# ProProject_audio_project_2024-04-28.net
KiCad netlist of a schematic drawn in EasyEDA Pro
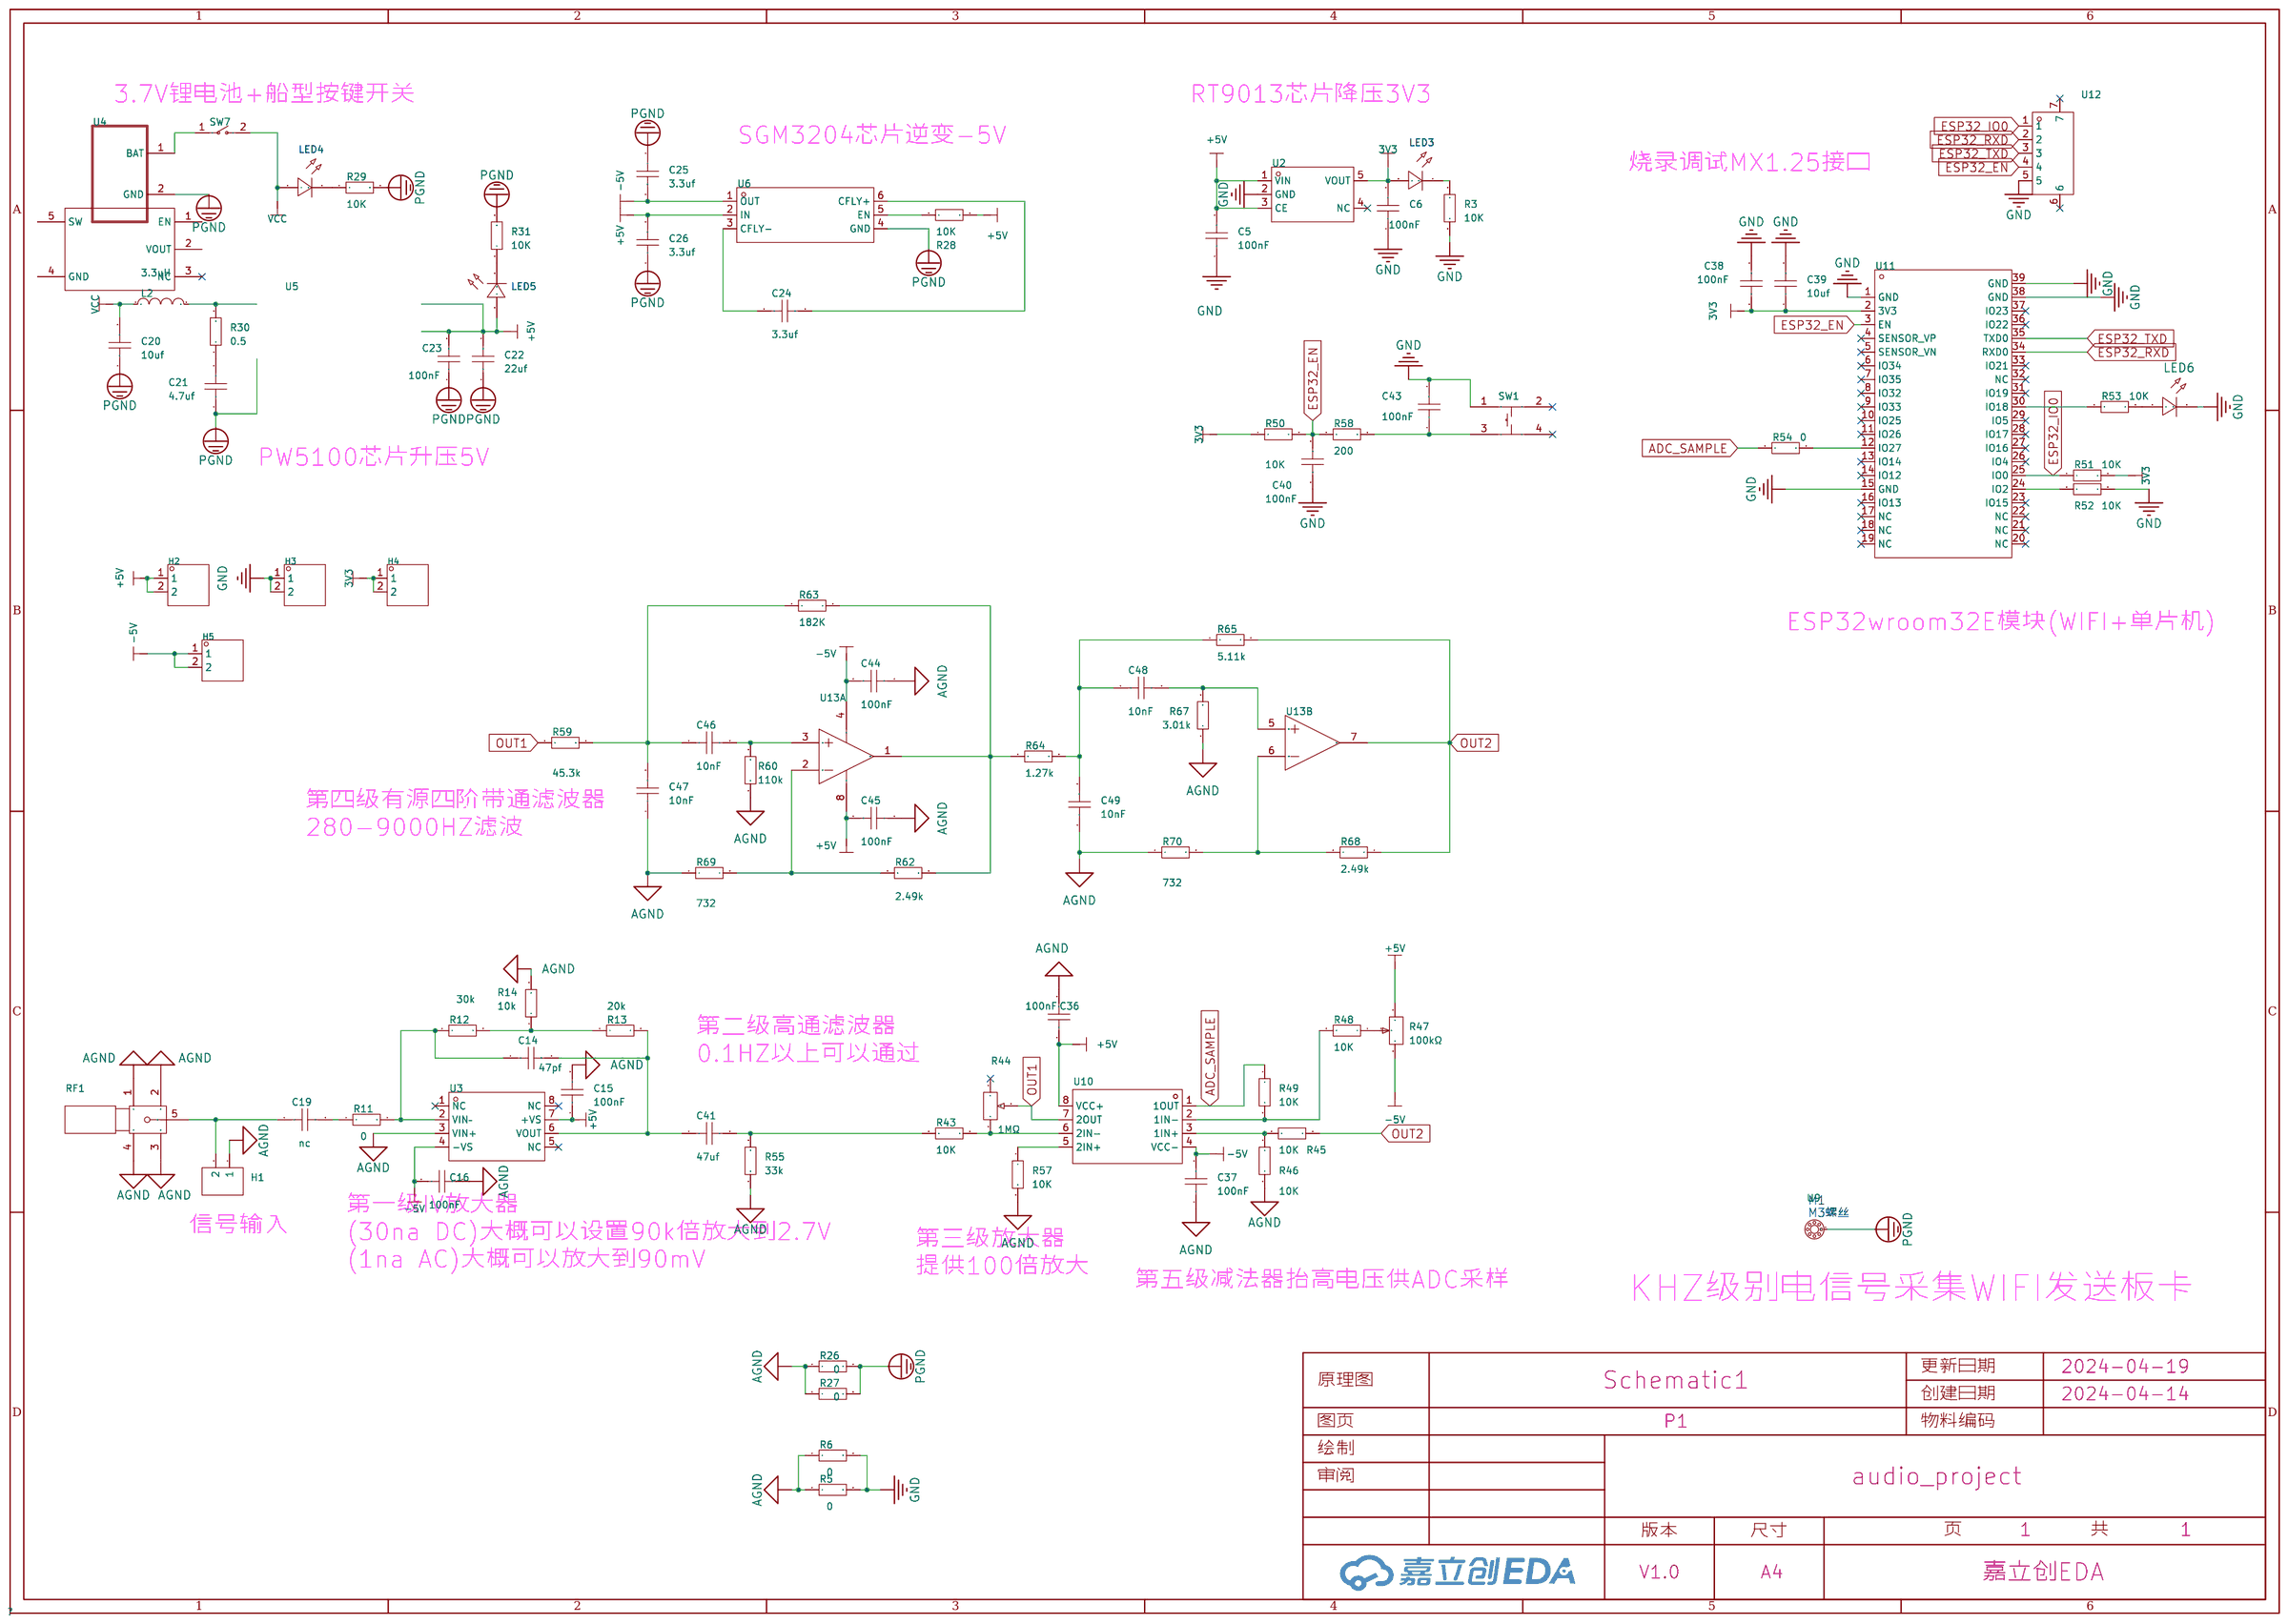
[diagram p0: schematic sheet]

(export (version "E")
  (design (tool "Eeschema 10.0.6"))
  (components
    (comp (ref "C5")
      (value "100nF")
      (footprint "easyedapro:C0805")
      (libsource (lib "easyedapro") (part "CapAcitance"))
    )
    (comp (ref "C6")
      (value "100nF")
      (footprint "easyedapro:C0805")
      (libsource (lib "easyedapro") (part "CapAcitance"))
    )
    (comp (ref "C14")
      (value "47pf")
      (footprint "easyedapro:C0805")
      (libsource (lib "easyedapro") (part "CapAcitance"))
    )
    (comp (ref "C15")
      (value "100nF")
      (footprint "easyedapro:C0805")
      (libsource (lib "easyedapro") (part "CapAcitance"))
    )
    (comp (ref "C16")
      (value "100nF")
      (footprint "easyedapro:C0805")
      (libsource (lib "easyedapro") (part "CapAcitance"))
    )
    (comp (ref "C19")
      (value "nc")
      (footprint "easyedapro:C0805")
      (libsource (lib "easyedapro") (part "CapAcitance"))
    )
    (comp (ref "C20")
      (value "10uf")
      (footprint "easyedapro:C0805")
      (libsource (lib "easyedapro") (part "CapAcitance"))
    )
    (comp (ref "C21")
      (value "4.7uf")
      (footprint "easyedapro:C0805")
      (libsource (lib "easyedapro") (part "CapAcitance"))
    )
    (comp (ref "C22")
      (value "22uf")
      (footprint "easyedapro:C0805")
      (libsource (lib "easyedapro") (part "CapAcitance"))
    )
    (comp (ref "C23")
      (value "100nF")
      (footprint "easyedapro:C0805")
      (libsource (lib "easyedapro") (part "CapAcitance"))
    )
    (comp (ref "C24")
      (value "3.3uf")
      (footprint "easyedapro:C0805")
      (libsource (lib "easyedapro") (part "CapAcitance"))
    )
    (comp (ref "C25")
      (value "3.3uf")
      (footprint "easyedapro:C0805")
      (libsource (lib "easyedapro") (part "CapAcitance"))
    )
    (comp (ref "C26")
      (value "3.3uf")
      (footprint "easyedapro:C0805")
      (libsource (lib "easyedapro") (part "CapAcitance"))
    )
    (comp (ref "C36")
      (value "100nF")
      (footprint "easyedapro:C0805")
      (libsource (lib "easyedapro") (part "CapAcitance"))
    )
    (comp (ref "C37")
      (value "100nF")
      (footprint "easyedapro:C0805")
      (libsource (lib "easyedapro") (part "CapAcitance"))
    )
    (comp (ref "C38")
      (value "100nF")
      (footprint "easyedapro:C0805")
      (libsource (lib "easyedapro") (part "CapAcitance"))
    )
    (comp (ref "C39")
      (value "10uf")
      (footprint "easyedapro:C0805")
      (libsource (lib "easyedapro") (part "CapAcitance"))
    )
    (comp (ref "C40")
      (value "100nF")
      (footprint "easyedapro:C0805")
      (libsource (lib "easyedapro") (part "CapAcitance"))
    )
    (comp (ref "C41")
      (value "47uf")
      (footprint "easyedapro:C0805")
      (libsource (lib "easyedapro") (part "CapAcitance"))
    )
    (comp (ref "C43")
      (value "100nF")
      (footprint "easyedapro:C0805")
      (libsource (lib "easyedapro") (part "CapAcitance"))
    )
    (comp (ref "C44")
      (value "100nF")
      (footprint "easyedapro:C0805")
      (libsource (lib "easyedapro") (part "CapAcitance"))
    )
    (comp (ref "C45")
      (value "100nF")
      (footprint "easyedapro:C0805")
      (libsource (lib "easyedapro") (part "CapAcitance"))
    )
    (comp (ref "C46")
      (value "10nF")
      (footprint "easyedapro:C0805")
      (libsource (lib "easyedapro") (part "CapAcitance"))
    )
    (comp (ref "C47")
      (value "10nF")
      (footprint "easyedapro:C0805")
      (libsource (lib "easyedapro") (part "CapAcitance"))
    )
    (comp (ref "C48")
      (value "10nF")
      (footprint "easyedapro:C0805")
      (libsource (lib "easyedapro") (part "CapAcitance"))
    )
    (comp (ref "C49")
      (value "10nF")
      (footprint "easyedapro:C0805")
      (libsource (lib "easyedapro") (part "CapAcitance"))
    )
    (comp (ref "H1")
      (value "~")
      (footprint "easyedapro:HDR-TH_2P-P2.54-V-F")
      (libsource (lib "easyedapro") (part "Header-Female-2.54_1x2"))
    )
    (comp (ref "H2")
      (value "~")
      (footprint "easyedapro:HDR-TH_2P-P2.54-V-M-1")
      (libsource (lib "easyedapro") (part "210S-1*2P L=11.6MMGold-plated black"))
    )
    (comp (ref "H3")
      (value "~")
      (footprint "easyedapro:HDR-TH_2P-P2.54-V-M-1")
      (libsource (lib "easyedapro") (part "210S-1*2P L=11.6MMGold-plated black"))
    )
    (comp (ref "H4")
      (value "~")
      (footprint "easyedapro:HDR-TH_2P-P2.54-V-M-1")
      (libsource (lib "easyedapro") (part "210S-1*2P L=11.6MMGold-plated black"))
    )
    (comp (ref "H5")
      (value "~")
      (footprint "easyedapro:HDR-TH_2P-P2.54-V-M-1")
      (libsource (lib "easyedapro") (part "210S-1*2P L=11.6MMGold-plated black"))
    )
    (comp (ref "L2")
      (value "3.3uH")
      (footprint "easyedapro:IND-SMD_L4.0-W4.0_FNR40XXS")
      (description "电感值:3.3uH;精度:±20%;额定电流:2.6A;饱和电流(Isat):3.6A;")
      (fields (field (name "Manufacturer Part") "FNR4030S3R3MT") (field (name "Manufacturer") "cjiang(长江微电)"))
      (libsource (lib "easyedapro") (part "FNR4030S3R3MT"))
    )
    (comp (ref "LED3")
      (value "~")
      (footprint "easyedapro:LED_0805")
      (libsource (lib "easyedapro") (part "LED_G"))
    )
    (comp (ref "LED4")
      (value "~")
      (footprint "easyedapro:LED_0805")
      (libsource (lib "easyedapro") (part "LED_G"))
    )
    (comp (ref "LED5")
      (value "~")
      (footprint "easyedapro:LED_0805")
      (libsource (lib "easyedapro") (part "LED_G"))
    )
    (comp (ref "LED6")
      (value "~")
      (footprint "easyedapro:LED_0805")
      (libsource (lib "easyedapro") (part "LED_R"))
    )
    (comp (ref "R3") (value "10K") (footprint "easyedapro:R0603") (libsource (lib "easyedapro") (part "电阻")))
    (comp (ref "R5") (value "0") (footprint "easyedapro:R0603") (libsource (lib "easyedapro") (part "电阻")))
    (comp (ref "R6") (value "0") (footprint "easyedapro:R0603") (libsource (lib "easyedapro") (part "电阻")))
    (comp (ref "R11") (value "0") (footprint "easyedapro:R0603") (libsource (lib "easyedapro") (part "电阻")))
    (comp (ref "R12") (value "30k") (footprint "easyedapro:R0603") (libsource (lib "easyedapro") (part "电阻")))
    (comp (ref "R13") (value "20k") (footprint "easyedapro:R0603") (libsource (lib "easyedapro") (part "电阻")))
    (comp (ref "R14") (value "10k") (footprint "easyedapro:R0603") (libsource (lib "easyedapro") (part "电阻")))
    (comp (ref "R26") (value "0") (footprint "easyedapro:R0603") (libsource (lib "easyedapro") (part "电阻")))
    (comp (ref "R27") (value "0") (footprint "easyedapro:R0603") (libsource (lib "easyedapro") (part "电阻")))
    (comp (ref "R28") (value "10K") (footprint "easyedapro:R0603") (libsource (lib "easyedapro") (part "电阻")))
    (comp (ref "R29") (value "10K") (footprint "easyedapro:R0603") (libsource (lib "easyedapro") (part "电阻")))
    (comp (ref "R30") (value "0.5") (footprint "easyedapro:R0603") (libsource (lib "easyedapro") (part "电阻")))
    (comp (ref "R31") (value "10K") (footprint "easyedapro:R0603") (libsource (lib "easyedapro") (part "电阻")))
    (comp (ref "R43") (value "10K") (footprint "easyedapro:R0603") (libsource (lib "easyedapro") (part "电阻")))
    (comp (ref "R44")
      (value "1MΩ")
      (footprint "easyedapro:RES-ADJ-TH_3P-L7.1-W6.9-P2.50-L_3362P")
      (description "阻值:1MΩ;精度:±10%;")
      (fields (field (name "Manufacturer Part") "3362P-1-105") (field (name "Manufacturer") "BOCHEN(博晨)"))
      (libsource (lib "easyedapro") (part "3362P-1-105_C118945"))
    )
    (comp (ref "R45") (value "10K") (footprint "easyedapro:R0603") (libsource (lib "easyedapro") (part "电阻")))
    (comp (ref "R46") (value "10K") (footprint "easyedapro:R0603") (libsource (lib "easyedapro") (part "电阻")))
    (comp (ref "R47")
      (value "100kΩ")
      (footprint "easyedapro:RES-ADJ-TH_3296W")
      (description "阻值:100kΩ;精度:±10%;")
      (fields (field (name "Manufacturer Part") "3296W-1-104LF") (field (name "Manufacturer") "BOURNS"))
      (libsource (lib "easyedapro") (part "3296W-1-104LF"))
    )
    (comp (ref "R48") (value "10K") (footprint "easyedapro:R0603") (libsource (lib "easyedapro") (part "电阻")))
    (comp (ref "R49") (value "10K") (footprint "easyedapro:R0603") (libsource (lib "easyedapro") (part "电阻")))
    (comp (ref "R50") (value "10K") (footprint "easyedapro:R0603") (libsource (lib "easyedapro") (part "电阻")))
    (comp (ref "R51") (value "10K") (footprint "easyedapro:R0603") (libsource (lib "easyedapro") (part "电阻")))
    (comp (ref "R52") (value "10K") (footprint "easyedapro:R0603") (libsource (lib "easyedapro") (part "电阻")))
    (comp (ref "R53") (value "10K") (footprint "easyedapro:R0603") (libsource (lib "easyedapro") (part "电阻")))
    (comp (ref "R54") (value "0") (footprint "easyedapro:R0603") (libsource (lib "easyedapro") (part "电阻")))
    (comp (ref "R55") (value "33k") (footprint "easyedapro:R0603") (libsource (lib "easyedapro") (part "电阻")))
    (comp (ref "R57") (value "10K") (footprint "easyedapro:R0603") (libsource (lib "easyedapro") (part "电阻")))
    (comp (ref "R58") (value "200") (footprint "easyedapro:R0603") (libsource (lib "easyedapro") (part "电阻")))
    (comp (ref "R59")
      (value "45.3k")
      (footprint "easyedapro:R0603")
      (libsource (lib "easyedapro") (part "电阻"))
    )
    (comp (ref "R60")
      (value "110k")
      (footprint "easyedapro:R0603")
      (libsource (lib "easyedapro") (part "电阻"))
    )
    (comp (ref "R62")
      (value "2.49k")
      (footprint "easyedapro:R0603")
      (libsource (lib "easyedapro") (part "电阻"))
    )
    (comp (ref "R63")
      (value "182K")
      (footprint "easyedapro:R0603")
      (libsource (lib "easyedapro") (part "电阻"))
    )
    (comp (ref "R64")
      (value "1.27k")
      (footprint "easyedapro:R0603")
      (libsource (lib "easyedapro") (part "电阻"))
    )
    (comp (ref "R65")
      (value "5.11k")
      (footprint "easyedapro:R0603")
      (libsource (lib "easyedapro") (part "电阻"))
    )
    (comp (ref "R67")
      (value "3.01k")
      (footprint "easyedapro:R0603")
      (libsource (lib "easyedapro") (part "电阻"))
    )
    (comp (ref "R68")
      (value "2.49k")
      (footprint "easyedapro:R0603")
      (libsource (lib "easyedapro") (part "电阻"))
    )
    (comp (ref "R69") (value "732") (footprint "easyedapro:R0603") (libsource (lib "easyedapro") (part "电阻")))
    (comp (ref "R70") (value "732") (footprint "easyedapro:R0603") (libsource (lib "easyedapro") (part "电阻")))
    (comp (ref "RF1")
      (value "BWSMA-KWE-Z001")
      (footprint "easyedapro:SMA-TH_BWSMA-KWE-Z001")
      (fields (field (name "Manufacturer") "BAT WIRELESS(蝙蝠无线)"))
      (libsource (lib "easyedapro") (part "BWSMA-KWE-Z001"))
    )
    (comp (ref "SW1")
      (value "K2-1808SN-A3SW-01")
      (footprint "easyedapro:SW-SMD_4P-L4.2-W3.3-P2.15-LS5.1")
      (fields (field (name "Manufacturer") "韩国韩荣"))
      (libsource (lib "easyedapro") (part "K2-1808SN-A3SW-01"))
    )
    (comp (ref "SW7")
      (value "KCD11-2P-R")
      (footprint "easyedapro:SW-TH_2P-L15.0-W10.5-P5.00_KCD11-2P-R")
      (description "带灯:无;引脚样式:焊片;额定电流:3A;额定电压(AC):250V;额定电压(DC):-;电路结构:单刀单掷;机械寿命:1万次;")
      (fields (field (name "Manufacturer") "SHOU HAN(首韩)"))
      (libsource (lib "easyedapro") (part "KCD11-2P-R"))
    )
    (comp (ref "U2")
      (value "RT9013-33GB-MS")
      (footprint "easyedapro:SOT-23-5_L2.9-W1.6-P0.95-LS2.8-BR")
      (description "输出类型:固定;最大输入电压:5.5V;输出电压:3.3V;输出电流:500mA;电源纹波抑制比(PSRR):75dB@(1kHz);输出极性:正极;")
      (fields (field (name "Manufacturer") "MSKSEMI(美森科)"))
      (libsource (lib "easyedapro") (part "RT9013-33GB-MS"))
    )
    (comp (ref "U3")
      (value "OPA657U")
      (footprint "easyedapro:SOIC-8_L4.9-W3.9-P1.27-LS6.0-TL")
      (description "1.6GHz、低噪声、FET 输入运算放大器 8-SOIC -40 to 85")
      (fields (field (name "Manufacturer") "TI(德州仪器)"))
      (libsource (lib "easyedapro") (part "OPA657U"))
    )
    (comp (ref "U4") (value "~") (footprint "easyedapro:两个焊盘") (libsource (lib "easyedapro") (part "两个焊盘")))
    (comp (ref "U5")
      (value "3c0bada92d29401ea73ee46ec49cffd6")
      (footprint "easyedapro:SOT-23-5_L2.9-W1.6-P0.95-LS2.8-TL")
      (description "锂电池DC-DC高效同步升压变换器")
      (libsource (lib "easyedapro") (part "PW5100"))
    )
    (comp (ref "U6")
      (value "SGM3204YN6G/TR")
      (footprint "easyedapro:SOT-23-6_L2.9-W1.6-P0.95-LS2.8-BR")
      (description "功能类型:电荷泵;输入电压:1.4V~5.5V;输出电压:-5.5V~-1.4V;输出电流(最大值):200mA;")
      (fields (field (name "Manufacturer") "SGMICRO(圣邦微)"))
      (libsource (lib "easyedapro") (part "SGM3204YN6G/TR"))
    )
    (comp (ref "U9") (value "~") (libsource (lib "easyedapro") (part "M3焊盘")))
    (comp (ref "U10")
      (value "LF353DR")
      (footprint "easyedapro:SOIC-8_L5.0-W4.0-P1.27-LS6.0-BL")
      (description "运放类型:J-FET;放大器组数:2;增益带宽积（GBP）:3MHz;压摆率（SR）:13 V/us;电源电压:±3.5V ~ 18V;各通道供电电流:3.6mA;")
      (fields (field (name "Manufacturer") "TI(德州仪器)"))
      (libsource (lib "easyedapro") (part "LF353DRG4"))
    )
    (comp (ref "U11")
      (value "ESP32-WROOM-32E")
      (footprint "easyedapro:WIFI-SMD_ESP32-WROOM-32E-A")
      (fields (field (name "Manufacturer") "ESPRESSIF(乐鑫)"))
      (libsource (lib "easyedapro") (part "ESP32-WROOM-32E-N4"))
    )
    (comp (ref "U12")
      (value "ZX-MX1.25-5PLT")
      (footprint "easyedapro:CONN-SMD_5P-P1.25_MEGASTAR_ZX-MX1.25-5PLT")
      (fields (field (name "Manufacturer") "Megastar(兆星)"))
      (libsource (lib "easyedapro") (part "ZX-MX1.25-5PLT"))
    )
    (comp (ref "U13")
      (value "OPA2182IDR")
      (footprint "easyedapro:SOIC-8_L4.9-W3.9-P1.27-LS6.0-BL")
      (description "放大器数:双路;增益带宽积(GBP):5MHz;输入偏置电流(Ib):50pA;输入失调电压(Vos):450nV;压摆率(SR):10V/us;带宽(-3db):-;轨到轨:-;")
      (fields (field (name "Manufacturer") "TI(德州仪器)"))
      (libsource (lib "easyedapro") (part "OPA2182IDR"))
    )
  )
  (nets
    (net (code "1") (name "+5V") (class "Default")
      (node (ref "C15") (pin "1") (pinfunction "1_1") (pintype "input"))
      (node (ref "C22") (pin "2") (pinfunction "2_2") (pintype "input"))
      (node (ref "C23") (pin "2") (pinfunction "2_2") (pintype "input"))
      (node (ref "C26") (pin "2") (pinfunction "2_2") (pintype "input"))
      (node (ref "C36") (pin "1") (pinfunction "1_1") (pintype "input"))
      (node (ref "C45") (pin "2") (pinfunction "2_2") (pintype "input"))
      (node (ref "C5") (pin "2") (pinfunction "2_2") (pintype "input"))
      (node (ref "H2") (pin "1") (pinfunction "1_1") (pintype "input"))
      (node (ref "H2") (pin "2") (pinfunction "2_2") (pintype "input"))
      (node (ref "LED5") (pin "2") (pinfunction "A_2") (pintype "input"))
      (node (ref "R28") (pin "2") (pinfunction "2_2") (pintype "input"))
      (node (ref "R47") (pin "1") (pinfunction "1_1") (pintype "input"))
      (node (ref "U10") (pin "8") (pinfunction "VCC+_8") (pintype "input"))
      (node (ref "U13") (pin "8") (pinfunction "V+_8") (pintype "unspecified"))
      (node (ref "U2") (pin "1") (pinfunction "VIN_1") (pintype "unspecified"))
      (node (ref "U2") (pin "3") (pinfunction "CE_3") (pintype "unspecified"))
      (node (ref "U3") (pin "7") (pinfunction "+VS_7") (pintype "input"))
      (node (ref "U6") (pin "2") (pinfunction "IN_2") (pintype "unspecified"))
    )
    (net (code "2") (name "-5V") (class "Default")
      (node (ref "C16") (pin "2") (pinfunction "2_2") (pintype "input"))
      (node (ref "C25") (pin "2") (pinfunction "2_2") (pintype "input"))
      (node (ref "C37") (pin "2") (pinfunction "2_2") (pintype "input"))
      (node (ref "C44") (pin "2") (pinfunction "2_2") (pintype "input"))
      (node (ref "H5") (pin "1") (pinfunction "1_1") (pintype "input"))
      (node (ref "H5") (pin "2") (pinfunction "2_2") (pintype "input"))
      (node (ref "R47") (pin "3") (pinfunction "3_3") (pintype "input"))
      (node (ref "U10") (pin "4") (pinfunction "VCC-_4") (pintype "input"))
      (node (ref "U13") (pin "4") (pinfunction "V-_4") (pintype "unspecified"))
      (node (ref "U3") (pin "4") (pinfunction "-VS_4") (pintype "input"))
      (node (ref "U6") (pin "1") (pinfunction "OUT_1") (pintype "unspecified"))
    )
    (net (code "3") (name "3V3") (class "Default")
      (node (ref "C38") (pin "2") (pinfunction "2_2") (pintype "input"))
      (node (ref "C39") (pin "1") (pinfunction "1_1") (pintype "input"))
      (node (ref "C6") (pin "2") (pinfunction "2_2") (pintype "input"))
      (node (ref "H4") (pin "1") (pinfunction "1_1") (pintype "input"))
      (node (ref "H4") (pin "2") (pinfunction "2_2") (pintype "input"))
      (node (ref "LED3") (pin "2") (pinfunction "A_2") (pintype "input"))
      (node (ref "R50") (pin "1") (pinfunction "1_1") (pintype "input"))
      (node (ref "R51") (pin "2") (pinfunction "2_2") (pintype "input"))
      (node (ref "U11") (pin "2") (pinfunction "3V3_2") (pintype "unspecified"))
      (node (ref "U2") (pin "5") (pinfunction "VOUT_5") (pintype "unspecified"))
    )
    (net (code "4") (name "ADC_SAMPLE") (class "Default")
      (node (ref "R49") (pin "1") (pinfunction "1_1") (pintype "input"))
      (node (ref "R54") (pin "1") (pinfunction "1_1") (pintype "input"))
      (node (ref "U10") (pin "1") (pinfunction "1OUT_1") (pintype "input"))
    )
    (net (code "5") (name "AGND") (class "Default")
      (node (ref "C15") (pin "2") (pinfunction "2_2") (pintype "input"))
      (node (ref "C16") (pin "1") (pinfunction "1_1") (pintype "input"))
      (node (ref "C36") (pin "2") (pinfunction "2_2") (pintype "input"))
      (node (ref "C37") (pin "1") (pinfunction "1_1") (pintype "input"))
      (node (ref "C44") (pin "1") (pinfunction "1_1") (pintype "input"))
      (node (ref "C45") (pin "1") (pinfunction "1_1") (pintype "input"))
      (node (ref "C47") (pin "1") (pinfunction "1_1") (pintype "input"))
      (node (ref "C49") (pin "1") (pinfunction "1_1") (pintype "input"))
      (node (ref "H1") (pin "1") (pinfunction "1_1") (pintype "input"))
      (node (ref "R14") (pin "2") (pinfunction "2_2") (pintype "input"))
      (node (ref "R26") (pin "1") (pinfunction "1_1") (pintype "input"))
      (node (ref "R27") (pin "1") (pinfunction "1_1") (pintype "input"))
      (node (ref "R46") (pin "1") (pinfunction "1_1") (pintype "input"))
      (node (ref "R5") (pin "1") (pinfunction "1_1") (pintype "input"))
      (node (ref "R55") (pin "1") (pinfunction "1_1") (pintype "input"))
      (node (ref "R57") (pin "2") (pinfunction "2_2") (pintype "input"))
      (node (ref "R6") (pin "1") (pinfunction "1_1") (pintype "input"))
      (node (ref "R60") (pin "1") (pinfunction "1_1") (pintype "input"))
      (node (ref "R67") (pin "1") (pinfunction "1_1") (pintype "input"))
      (node (ref "R69") (pin "1") (pinfunction "1_1") (pintype "input"))
      (node (ref "R70") (pin "1") (pinfunction "1_1") (pintype "input"))
      (node (ref "RF1") (pin "1") (pinfunction "1_1") (pintype "unspecified"))
      (node (ref "RF1") (pin "2") (pinfunction "2_2") (pintype "unspecified"))
      (node (ref "RF1") (pin "3") (pinfunction "3_3") (pintype "unspecified"))
      (node (ref "RF1") (pin "4") (pinfunction "4_4") (pintype "unspecified"))
      (node (ref "U3") (pin "3") (pinfunction "VIN+_3") (pintype "input"))
    )
    (net (code "6") (name "ESP32_EN") (class "Default")
      (node (ref "C40") (pin "2") (pinfunction "2_2") (pintype "input"))
      (node (ref "R50") (pin "2") (pinfunction "2_2") (pintype "input"))
      (node (ref "R58") (pin "1") (pinfunction "1_1") (pintype "input"))
      (node (ref "U11") (pin "3") (pinfunction "EN_3") (pintype "unspecified"))
      (node (ref "U12") (pin "4") (pinfunction "4_4") (pintype "unspecified"))
    )
    (net (code "7") (name "ESP32_IO0") (class "Default")
      (node (ref "R51") (pin "1") (pinfunction "1_1") (pintype "input"))
      (node (ref "U11") (pin "25") (pinfunction "IO0_25") (pintype "unspecified"))
      (node (ref "U12") (pin "1") (pinfunction "1_1") (pintype "unspecified"))
    )
    (net (code "8") (name "ESP32_RXD") (class "Default")
      (node (ref "U11") (pin "34") (pinfunction "RXD0_34") (pintype "unspecified"))
      (node (ref "U12") (pin "2") (pinfunction "2_2") (pintype "unspecified"))
    )
    (net (code "9") (name "ESP32_TXD") (class "Default")
      (node (ref "U11") (pin "35") (pinfunction "TXD0_35") (pintype "unspecified"))
      (node (ref "U12") (pin "3") (pinfunction "3_3") (pintype "unspecified"))
    )
    (net (code "10") (name "GND") (class "Default")
      (node (ref "C38") (pin "1") (pinfunction "1_1") (pintype "input"))
      (node (ref "C39") (pin "2") (pinfunction "2_2") (pintype "input"))
      (node (ref "C40") (pin "1") (pinfunction "1_1") (pintype "input"))
      (node (ref "C43") (pin "2") (pinfunction "2_2") (pintype "input"))
      (node (ref "C5") (pin "1") (pinfunction "1_1") (pintype "input"))
      (node (ref "C6") (pin "1") (pinfunction "1_1") (pintype "input"))
      (node (ref "H3") (pin "1") (pinfunction "1_1") (pintype "input"))
      (node (ref "H3") (pin "2") (pinfunction "2_2") (pintype "input"))
      (node (ref "LED6") (pin "1") (pinfunction "C_1") (pintype "input"))
      (node (ref "R3") (pin "2") (pinfunction "2_2") (pintype "input"))
      (node (ref "R5") (pin "2") (pinfunction "2_2") (pintype "input"))
      (node (ref "R52") (pin "2") (pinfunction "2_2") (pintype "input"))
      (node (ref "R6") (pin "2") (pinfunction "2_2") (pintype "input"))
      (node (ref "SW1") (pin "1") (pinfunction "1_1") (pintype "input"))
      (node (ref "U11") (pin "1") (pinfunction "GND_1") (pintype "unspecified"))
      (node (ref "U11") (pin "15") (pinfunction "GND_15") (pintype "unspecified"))
      (node (ref "U11") (pin "38") (pinfunction "GND_38") (pintype "unspecified"))
      (node (ref "U11") (pin "39") (pinfunction "GND_39") (pintype "unspecified"))
      (node (ref "U12") (pin "5") (pinfunction "5_5") (pintype "unspecified"))
      (node (ref "U2") (pin "2") (pinfunction "GND_2") (pintype "unspecified"))
    )
    (net (code "11") (name "Net-(C19-Pad1)") (class "Default")
      (node (ref "C19") (pin "1") (pinfunction "1_1") (pintype "input"))
      (node (ref "H1") (pin "2") (pinfunction "2_2") (pintype "input"))
      (node (ref "RF1") (pin "5") (pinfunction "5_5") (pintype "unspecified"))
    )
    (net (code "12") (name "Net-(C19-Pad2)") (class "Default")
      (node (ref "C19") (pin "2") (pinfunction "2_2") (pintype "input"))
      (node (ref "R11") (pin "1") (pinfunction "1_1") (pintype "input"))
    )
    (net (code "13") (name "Net-(C21-Pad2)") (class "Default")
      (node (ref "C21") (pin "2") (pinfunction "2_2") (pintype "input"))
      (node (ref "R30") (pin "1") (pinfunction "1_1") (pintype "input"))
    )
    (net (code "14") (name "Net-(C41-Pad2)") (class "Default")
      (node (ref "C41") (pin "2") (pinfunction "2_2") (pintype "input"))
      (node (ref "R43") (pin "2") (pinfunction "2_2") (pintype "input"))
      (node (ref "R55") (pin "2") (pinfunction "2_2") (pintype "input"))
    )
    (net (code "15") (name "Net-(C43-Pad1)") (class "Default")
      (node (ref "C43") (pin "1") (pinfunction "1_1") (pintype "input"))
      (node (ref "R58") (pin "2") (pinfunction "2_2") (pintype "input"))
      (node (ref "SW1") (pin "3") (pinfunction "3_3") (pintype "input"))
    )
    (net (code "16") (name "Net-(C46-Pad1)") (class "Default")
      (node (ref "C46") (pin "1") (pinfunction "1_1") (pintype "input"))
      (node (ref "C47") (pin "2") (pinfunction "2_2") (pintype "input"))
      (node (ref "R59") (pin "2") (pinfunction "2_2") (pintype "input"))
      (node (ref "R63") (pin "1") (pinfunction "1_1") (pintype "input"))
    )
    (net (code "17") (name "Net-(C48-Pad1)") (class "Default")
      (node (ref "C48") (pin "1") (pinfunction "1_1") (pintype "input"))
      (node (ref "C49") (pin "2") (pinfunction "2_2") (pintype "input"))
      (node (ref "R64") (pin "2") (pinfunction "2_2") (pintype "input"))
      (node (ref "R65") (pin "1") (pinfunction "1_1") (pintype "input"))
    )
    (net (code "18") (name "Net-(L2-Pad2)") (class "Default")
      (node (ref "L2") (pin "2") (pinfunction "2_2") (pintype "unspecified"))
      (node (ref "R30") (pin "2") (pinfunction "2_2") (pintype "input"))
    )
    (net (code "19") (name "Net-(LED3-C)") (class "Default")
      (node (ref "LED3") (pin "1") (pinfunction "C_1") (pintype "input"))
      (node (ref "R3") (pin "1") (pinfunction "1_1") (pintype "input"))
    )
    (net (code "20") (name "Net-(LED4-C)") (class "Default")
      (node (ref "LED4") (pin "1") (pinfunction "C_1") (pintype "input"))
      (node (ref "R29") (pin "1") (pinfunction "1_1") (pintype "input"))
    )
    (net (code "21") (name "Net-(LED5-C)") (class "Default")
      (node (ref "LED5") (pin "1") (pinfunction "C_1") (pintype "input"))
      (node (ref "R31") (pin "1") (pinfunction "1_1") (pintype "input"))
    )
    (net (code "22") (name "Net-(LED6-A)") (class "Default")
      (node (ref "LED6") (pin "2") (pinfunction "A_2") (pintype "input"))
      (node (ref "R53") (pin "2") (pinfunction "2_2") (pintype "input"))
    )
    (net (code "23") (name "Net-(R12-Pad2)") (class "Default")
      (node (ref "R12") (pin "2") (pinfunction "2_2") (pintype "input"))
      (node (ref "R13") (pin "1") (pinfunction "1_1") (pintype "input"))
      (node (ref "R14") (pin "1") (pinfunction "1_1") (pintype "input"))
    )
    (net (code "24") (name "Net-(R47-Pad2)") (class "Default")
      (node (ref "R47") (pin "2") (pinfunction "2_2") (pintype "input"))
      (node (ref "R48") (pin "1") (pinfunction "1_1") (pintype "input"))
    )
    (net (code "25") (name "Net-(U3-VIN–)") (class "Default")
      (node (ref "C14") (pin "1") (pinfunction "1_1") (pintype "input"))
      (node (ref "R11") (pin "2") (pinfunction "2_2") (pintype "input"))
      (node (ref "R12") (pin "1") (pinfunction "1_1") (pintype "input"))
      (node (ref "U3") (pin "2") (pinfunction "VIN–_2") (pintype "input"))
    )
    (net (code "26") (name "Net-(U3-VOUT)") (class "Default")
      (node (ref "C14") (pin "2") (pinfunction "2_2") (pintype "input"))
      (node (ref "C41") (pin "1") (pinfunction "1_1") (pintype "input"))
      (node (ref "R13") (pin "2") (pinfunction "2_2") (pintype "input"))
      (node (ref "U3") (pin "6") (pinfunction "VOUT_6") (pintype "input"))
    )
    (net (code "27") (name "Net-(U4-BAT)") (class "Default")
      (node (ref "SW7") (pin "1") (pinfunction "1_1") (pintype "unspecified"))
      (node (ref "U4") (pin "1") (pinfunction "BAT_1") (pintype "input"))
    )
    (net (code "28") (name "Net-(U6-CFLY+)") (class "Default")
      (node (ref "C24") (pin "1") (pinfunction "1_1") (pintype "input"))
      (node (ref "U6") (pin "6") (pinfunction "CFLY+_6") (pintype "unspecified"))
    )
    (net (code "29") (name "Net-(U6-CFLY-)") (class "Default")
      (node (ref "C24") (pin "2") (pinfunction "2_2") (pintype "input"))
      (node (ref "U6") (pin "3") (pinfunction "CFLY-_3") (pintype "unspecified"))
    )
    (net (code "30") (name "Net-(U6-EN)") (class "Default")
      (node (ref "R28") (pin "1") (pinfunction "1_1") (pintype "input"))
      (node (ref "U6") (pin "5") (pinfunction "EN_5") (pintype "unspecified"))
    )
    (net (code "31") (name "Net-(U10-1IN+)") (class "Default")
      (node (ref "R45") (pin "1") (pinfunction "1_1") (pintype "input"))
      (node (ref "R46") (pin "2") (pinfunction "2_2") (pintype "input"))
      (node (ref "U10") (pin "3") (pinfunction "1IN+_3") (pintype "input"))
    )
    (net (code "32") (name "Net-(U10-1IN-)") (class "Default")
      (node (ref "R48") (pin "2") (pinfunction "2_2") (pintype "input"))
      (node (ref "R49") (pin "2") (pinfunction "2_2") (pintype "input"))
      (node (ref "U10") (pin "2") (pinfunction "1IN-_2") (pintype "input"))
    )
    (net (code "33") (name "Net-(U10-2IN+)") (class "Default")
      (node (ref "R57") (pin "1") (pinfunction "1_1") (pintype "input"))
      (node (ref "U10") (pin "5") (pinfunction "2IN+_5") (pintype "input"))
    )
    (net (code "34") (name "Net-(U10-2IN-)") (class "Default")
      (node (ref "R43") (pin "1") (pinfunction "1_1") (pintype "input"))
      (node (ref "R44") (pin "3") (pinfunction "3_3") (pintype "input"))
      (node (ref "U10") (pin "6") (pinfunction "2IN-_6") (pintype "input"))
    )
    (net (code "35") (name "Net-(U11-IO2)") (class "Default")
      (node (ref "R52") (pin "1") (pinfunction "1_1") (pintype "input"))
      (node (ref "U11") (pin "24") (pinfunction "IO2_24") (pintype "unspecified"))
    )
    (net (code "36") (name "Net-(U11-IO18)") (class "Default")
      (node (ref "R53") (pin "1") (pinfunction "1_1") (pintype "input"))
      (node (ref "U11") (pin "30") (pinfunction "IO18_30") (pintype "unspecified"))
    )
    (net (code "37") (name "Net-(U11-IO27)") (class "Default")
      (node (ref "R54") (pin "2") (pinfunction "2_2") (pintype "input"))
      (node (ref "U11") (pin "12") (pinfunction "IO27_12") (pintype "unspecified"))
    )
    (net (code "38") (name "Net-(U13A-IN_A+)") (class "Default")
      (node (ref "C46") (pin "2") (pinfunction "2_2") (pintype "input"))
      (node (ref "R60") (pin "2") (pinfunction "2_2") (pintype "input"))
      (node (ref "U13") (pin "3") (pinfunction "IN_A+_3") (pintype "unspecified"))
    )
    (net (code "39") (name "Net-(U13A-IN_A-)") (class "Default")
      (node (ref "R62") (pin "1") (pinfunction "1_1") (pintype "input"))
      (node (ref "R69") (pin "2") (pinfunction "2_2") (pintype "input"))
      (node (ref "U13") (pin "2") (pinfunction "IN_A-_2") (pintype "unspecified"))
    )
    (net (code "40") (name "Net-(U13A-OUT_A)") (class "Default")
      (node (ref "R62") (pin "2") (pinfunction "2_2") (pintype "input"))
      (node (ref "R63") (pin "2") (pinfunction "2_2") (pintype "input"))
      (node (ref "R64") (pin "1") (pinfunction "1_1") (pintype "input"))
      (node (ref "U13") (pin "1") (pinfunction "OUT_A_1") (pintype "output"))
    )
    (net (code "41") (name "Net-(U13B-IN_B+)") (class "Default")
      (node (ref "C48") (pin "2") (pinfunction "2_2") (pintype "input"))
      (node (ref "R67") (pin "2") (pinfunction "2_2") (pintype "input"))
      (node (ref "U13") (pin "5") (pinfunction "IN_B+_5") (pintype "unspecified"))
    )
    (net (code "42") (name "Net-(U13B-IN_B-)") (class "Default")
      (node (ref "R68") (pin "2") (pinfunction "2_2") (pintype "input"))
      (node (ref "R70") (pin "2") (pinfunction "2_2") (pintype "input"))
      (node (ref "U13") (pin "6") (pinfunction "IN_B-_6") (pintype "unspecified"))
    )
    (net (code "43") (name "OUT1") (class "Default")
      (node (ref "R44") (pin "2") (pinfunction "2_2") (pintype "input"))
      (node (ref "R59") (pin "1") (pinfunction "1_1") (pintype "input"))
      (node (ref "U10") (pin "7") (pinfunction "2OUT_7") (pintype "input"))
    )
    (net (code "44") (name "OUT2") (class "Default")
      (node (ref "R45") (pin "2") (pinfunction "2_2") (pintype "input"))
      (node (ref "R65") (pin "2") (pinfunction "2_2") (pintype "input"))
      (node (ref "R68") (pin "1") (pinfunction "1_1") (pintype "input"))
      (node (ref "U13") (pin "7") (pinfunction "OUT_B_7") (pintype "output"))
    )
    (net (code "45") (name "PGND") (class "Default")
      (node (ref "C20") (pin "1") (pinfunction "1_1") (pintype "input"))
      (node (ref "C21") (pin "1") (pinfunction "1_1") (pintype "input"))
      (node (ref "C22") (pin "1") (pinfunction "1_1") (pintype "input"))
      (node (ref "C23") (pin "1") (pinfunction "1_1") (pintype "input"))
      (node (ref "C25") (pin "1") (pinfunction "1_1") (pintype "input"))
      (node (ref "C26") (pin "1") (pinfunction "1_1") (pintype "input"))
      (node (ref "R26") (pin "2") (pinfunction "2_2") (pintype "input"))
      (node (ref "R27") (pin "2") (pinfunction "2_2") (pintype "input"))
      (node (ref "R29") (pin "2") (pinfunction "2_2") (pintype "input"))
      (node (ref "R31") (pin "2") (pinfunction "2_2") (pintype "input"))
      (node (ref "U4") (pin "2") (pinfunction "GND_2") (pintype "input"))
      (node (ref "U6") (pin "4") (pinfunction "GND_4") (pintype "unspecified"))
      (node (ref "U9") (pin "1") (pinfunction "1_1") (pintype "input"))
    )
    (net (code "46") (name "VCC") (class "Default")
      (node (ref "C20") (pin "2") (pinfunction "2_2") (pintype "input"))
      (node (ref "L2") (pin "1") (pinfunction "1_1") (pintype "unspecified"))
      (node (ref "LED4") (pin "2") (pinfunction "A_2") (pintype "input"))
      (node (ref "SW7") (pin "2") (pinfunction "2_2") (pintype "unspecified"))
    )
    (net (code "47") (name "unconnected-(R44-Pad1)") (class "Default")
      (node (ref "R44") (pin "1") (pinfunction "1_1") (pintype "input+no_connect"))
    )
    (net (code "48") (name "unconnected-(SW1-Pad2)") (class "Default")
      (node (ref "SW1") (pin "2") (pinfunction "2_2") (pintype "input+no_connect"))
    )
    (net (code "49") (name "unconnected-(SW1-Pad4)") (class "Default")
      (node (ref "SW1") (pin "4") (pinfunction "4_4") (pintype "input+no_connect"))
    )
    (net (code "50") (name "unconnected-(U2-NC-Pad4)") (class "Default")
      (node (ref "U2") (pin "4") (pinfunction "NC_4") (pintype "unspecified+no_connect"))
    )
    (net (code "51") (name "unconnected-(U3-NC-Pad1)") (class "Default")
      (node (ref "U3") (pin "1") (pinfunction "NC_1") (pintype "input+no_connect"))
    )
    (net (code "52") (name "unconnected-(U3-NC-Pad5)") (class "Default")
      (node (ref "U3") (pin "5") (pinfunction "NC_5") (pintype "input+no_connect"))
    )
    (net (code "53") (name "unconnected-(U3-NC-Pad8)") (class "Default")
      (node (ref "U3") (pin "8") (pinfunction "NC_8") (pintype "input+no_connect"))
    )
    (net (code "54") (name "unconnected-(U5-EN-Pad1)") (class "Default")
      (node (ref "U5") (pin "1") (pinfunction "EN_1") (pintype "input"))
    )
    (net (code "55") (name "unconnected-(U5-GND-Pad4)") (class "Default")
      (node (ref "U5") (pin "4") (pinfunction "GND_4") (pintype "input"))
    )
    (net (code "56") (name "unconnected-(U5-NC-Pad3)") (class "Default")
      (node (ref "U5") (pin "3") (pinfunction "NC_3") (pintype "input+no_connect"))
    )
    (net (code "57") (name "unconnected-(U5-SW-Pad5)") (class "Default")
      (node (ref "U5") (pin "5") (pinfunction "SW_5") (pintype "input"))
    )
    (net (code "58") (name "unconnected-(U5-VOUT-Pad2)") (class "Default")
      (node (ref "U5") (pin "2") (pinfunction "VOUT_2") (pintype "input"))
    )
    (net (code "59") (name "unconnected-(U11-IO4-Pad26)") (class "Default")
      (node (ref "U11") (pin "26") (pinfunction "IO4_26") (pintype "unspecified+no_connect"))
    )
    (net (code "60") (name "unconnected-(U11-IO5-Pad29)") (class "Default")
      (node (ref "U11") (pin "29") (pinfunction "IO5_29") (pintype "unspecified+no_connect"))
    )
    (net (code "61") (name "unconnected-(U11-IO12-Pad14)") (class "Default")
      (node (ref "U11") (pin "14") (pinfunction "IO12_14") (pintype "unspecified+no_connect"))
    )
    (net (code "62") (name "unconnected-(U11-IO13-Pad16)") (class "Default")
      (node (ref "U11") (pin "16") (pinfunction "IO13_16") (pintype "unspecified+no_connect"))
    )
    (net (code "63") (name "unconnected-(U11-IO14-Pad13)") (class "Default")
      (node (ref "U11") (pin "13") (pinfunction "IO14_13") (pintype "unspecified+no_connect"))
    )
    (net (code "64") (name "unconnected-(U11-IO15-Pad23)") (class "Default")
      (node (ref "U11") (pin "23") (pinfunction "IO15_23") (pintype "unspecified+no_connect"))
    )
    (net (code "65") (name "unconnected-(U11-IO16-Pad27)") (class "Default")
      (node (ref "U11") (pin "27") (pinfunction "IO16_27") (pintype "unspecified+no_connect"))
    )
    (net (code "66") (name "unconnected-(U11-IO17-Pad28)") (class "Default")
      (node (ref "U11") (pin "28") (pinfunction "IO17_28") (pintype "unspecified+no_connect"))
    )
    (net (code "67") (name "unconnected-(U11-IO19-Pad31)") (class "Default")
      (node (ref "U11") (pin "31") (pinfunction "IO19_31") (pintype "unspecified+no_connect"))
    )
    (net (code "68") (name "unconnected-(U11-IO21-Pad33)") (class "Default")
      (node (ref "U11") (pin "33") (pinfunction "IO21_33") (pintype "unspecified+no_connect"))
    )
    (net (code "69") (name "unconnected-(U11-IO22-Pad36)") (class "Default")
      (node (ref "U11") (pin "36") (pinfunction "IO22_36") (pintype "unspecified+no_connect"))
    )
    (net (code "70") (name "unconnected-(U11-IO23-Pad37)") (class "Default")
      (node (ref "U11") (pin "37") (pinfunction "IO23_37") (pintype "unspecified+no_connect"))
    )
    (net (code "71") (name "unconnected-(U11-IO25-Pad10)") (class "Default")
      (node (ref "U11") (pin "10") (pinfunction "IO25_10") (pintype "unspecified+no_connect"))
    )
    (net (code "72") (name "unconnected-(U11-IO26-Pad11)") (class "Default")
      (node (ref "U11") (pin "11") (pinfunction "IO26_11") (pintype "unspecified+no_connect"))
    )
    (net (code "73") (name "unconnected-(U11-IO32-Pad8)") (class "Default")
      (node (ref "U11") (pin "8") (pinfunction "IO32_8") (pintype "unspecified+no_connect"))
    )
    (net (code "74") (name "unconnected-(U11-IO33-Pad9)") (class "Default")
      (node (ref "U11") (pin "9") (pinfunction "IO33_9") (pintype "unspecified+no_connect"))
    )
    (net (code "75") (name "unconnected-(U11-IO34-Pad6)") (class "Default")
      (node (ref "U11") (pin "6") (pinfunction "IO34_6") (pintype "unspecified+no_connect"))
    )
    (net (code "76") (name "unconnected-(U11-IO35-Pad7)") (class "Default")
      (node (ref "U11") (pin "7") (pinfunction "IO35_7") (pintype "unspecified+no_connect"))
    )
    (net (code "77") (name "unconnected-(U11-NC-Pad17)") (class "Default")
      (node (ref "U11") (pin "17") (pinfunction "NC_17") (pintype "unspecified+no_connect"))
    )
    (net (code "78") (name "unconnected-(U11-NC-Pad18)") (class "Default")
      (node (ref "U11") (pin "18") (pinfunction "NC_18") (pintype "unspecified+no_connect"))
    )
    (net (code "79") (name "unconnected-(U11-NC-Pad19)") (class "Default")
      (node (ref "U11") (pin "19") (pinfunction "NC_19") (pintype "unspecified+no_connect"))
    )
    (net (code "80") (name "unconnected-(U11-NC-Pad20)") (class "Default")
      (node (ref "U11") (pin "20") (pinfunction "NC_20") (pintype "unspecified+no_connect"))
    )
    (net (code "81") (name "unconnected-(U11-NC-Pad21)") (class "Default")
      (node (ref "U11") (pin "21") (pinfunction "NC_21") (pintype "unspecified+no_connect"))
    )
    (net (code "82") (name "unconnected-(U11-NC-Pad22)") (class "Default")
      (node (ref "U11") (pin "22") (pinfunction "NC_22") (pintype "unspecified+no_connect"))
    )
    (net (code "83") (name "unconnected-(U11-NC-Pad32)") (class "Default")
      (node (ref "U11") (pin "32") (pinfunction "NC_32") (pintype "unspecified+no_connect"))
    )
    (net (code "84") (name "unconnected-(U11-SENSOR_VN-Pad5)") (class "Default")
      (node (ref "U11") (pin "5") (pinfunction "SENSOR_VN_5") (pintype "unspecified+no_connect"))
    )
    (net (code "85") (name "unconnected-(U11-SENSOR_VP-Pad4)") (class "Default")
      (node (ref "U11") (pin "4") (pinfunction "SENSOR_VP_4") (pintype "unspecified+no_connect"))
    )
    (net (code "86") (name "unconnected-(U12-Pad6)") (class "Default")
      (node (ref "U12") (pin "6") (pinfunction "6_6") (pintype "unspecified+no_connect"))
    )
    (net (code "87") (name "unconnected-(U12-Pad7)") (class "Default")
      (node (ref "U12") (pin "7") (pinfunction "7_7") (pintype "unspecified+no_connect"))
    )
  )
)
